# Sheet1.net
KiCad netlist of a schematic drawn in Altium Designer
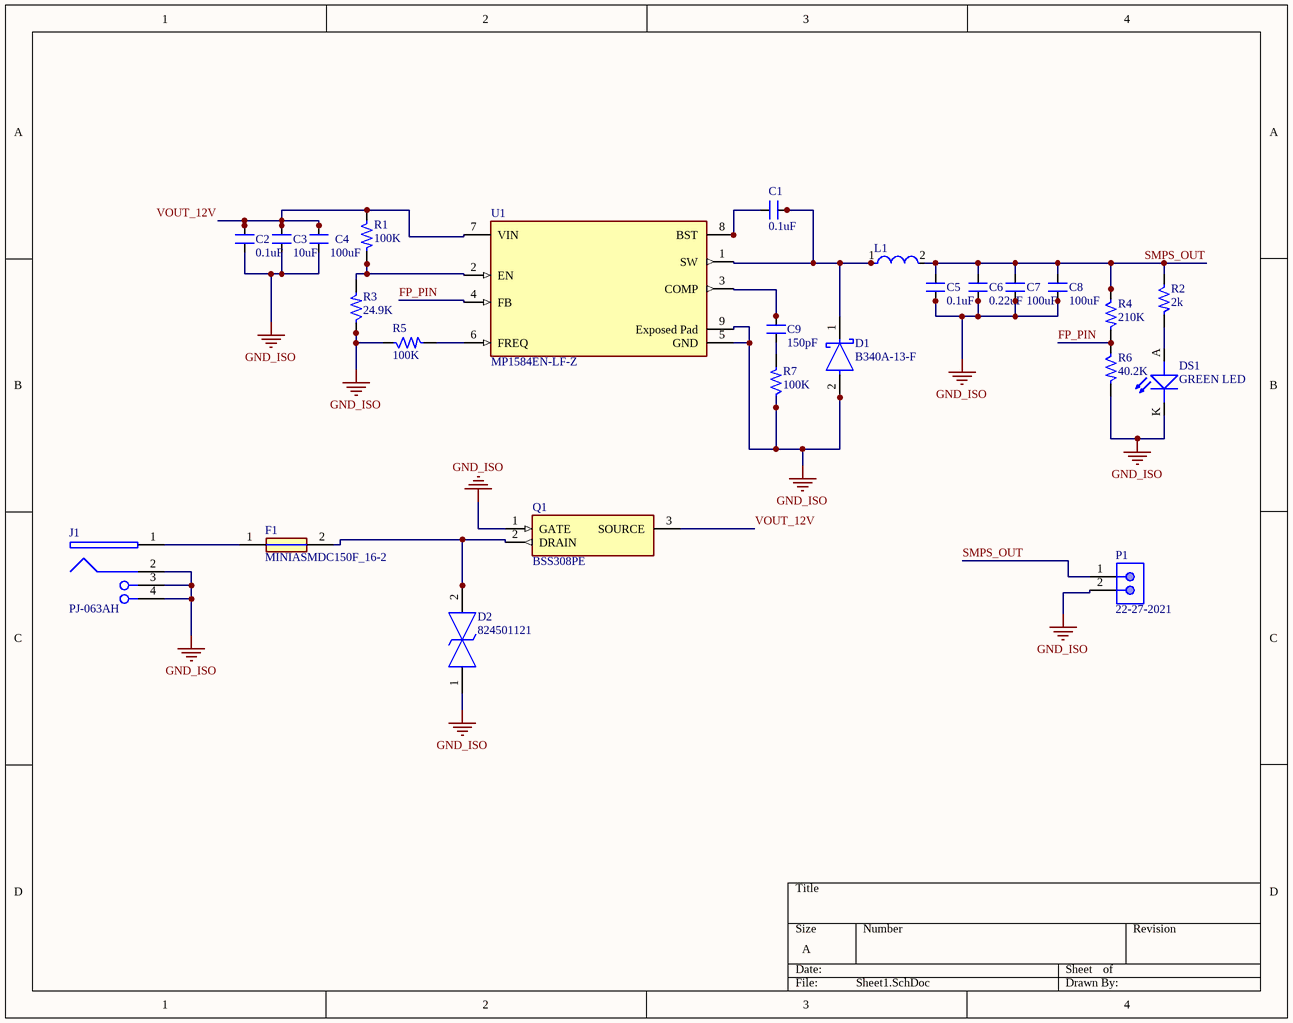
[diagram p0: Sheet1.SchDoc]

(export (version "E")
  (design (tool "Eeschema 10.0.6"))
  (components
    (comp (ref "C1")
      (value "0.1uF")
      (footprint "CAP_0805")
      (description "0.1µF ±20% 50V Ceramic Capacitor X7R 0805 (2012 Metric)")
      (fields
        (field (name "MANUFACTURER") "Samsung Electro-Mechanics")
        (field (name "MANUFACTURER PART NUMBER") "CL21B104MBCNNNC")
      )
      (libsource (lib "ESTEEMPCBLIB") (part "CAP_0.1uF-50V-20%-0805"))
    )
    (comp (ref "C2")
      (value "0.1uF")
      (footprint "CAP_0805")
      (description "0.1µF ±20% 50V Ceramic Capacitor X7R 0805 (2012 Metric)")
      (fields
        (field (name "MANUFACTURER") "Samsung Electro-Mechanics")
        (field (name "MANUFACTURER PART NUMBER") "CL21B104MBCNNNC")
      )
      (libsource (lib "ESTEEMPCBLIB") (part "CAP_0.1uF-50V-20%-0805"))
    )
    (comp (ref "C3")
      (value "10uF")
      (footprint "CAP_1206")
      (description "10µF ±10% 50V Ceramic Capacitor X7R 1206 (3216 Metric)")
      (fields
        (field (name "MANUFACTURER") "KEMET")
        (field (name "MANUFACTURER PART NUMBER") "CL31B106KBHNNNE")
      )
      (libsource (lib "ESTEEMPCBLIB") (part "CAP_10uF-50V-10%-1206"))
    )
    (comp (ref "C4")
      (value "100uF")
      (footprint "CAP_1206")
      (description "100µF ±5% 50V Ceramic Capacitor X7R 1206 (3216 Metric)")
      (fields
        (field (name "MANUFACTURER") "KEMET")
        (field (name "MANUFACTURER PART NUMBER") "C1206C104J5RACTU")
      )
      (libsource (lib "ESTEEMPCBLIB") (part "CAP_0.1uF-50V-5%-1206"))
    )
    (comp (ref "C5")
      (value "0.1uF")
      (footprint "CAP_0805")
      (description "0.1µF ±20% 50V Ceramic Capacitor X7R 0805 (2012 Metric)")
      (fields
        (field (name "MANUFACTURER") "Samsung Electro-Mechanics")
        (field (name "MANUFACTURER PART NUMBER") "CL21B104MBCNNNC")
      )
      (libsource (lib "ESTEEMPCBLIB") (part "CAP_0.1uF-50V-20%-0805"))
    )
    (comp (ref "C6")
      (value "0.22uF")
      (footprint "CAP_0805")
      (description "0.22µF ±10% 50V Ceramic Capacitor X7R 0805 (2012 Metric)")
      (fields
        (field (name "MANUFACTURER") "Murata")
        (field (name "MANUFACTURER PART NUMBER") "GRM21BR71H224KA01L")
      )
      (libsource (lib "ESTEEMPCBLIB") (part "CAP_0.22uF-50V-10%-0805"))
    )
    (comp (ref "C7")
      (value "100uF")
      (footprint "CAP_1206")
      (description "100µF ±5% 50V Ceramic Capacitor X7R 1206 (3216 Metric)")
      (fields
        (field (name "MANUFACTURER") "KEMET")
        (field (name "MANUFACTURER PART NUMBER") "C1206C104J5RACTU")
      )
      (libsource (lib "ESTEEMPCBLIB") (part "CAP_0.1uF-50V-5%-1206"))
    )
    (comp (ref "C8")
      (value "100uF")
      (footprint "CAP_1206")
      (description "100µF ±5% 50V Ceramic Capacitor X7R 1206 (3216 Metric)")
      (fields
        (field (name "MANUFACTURER") "KEMET")
        (field (name "MANUFACTURER PART NUMBER") "C1206C104J5RACTU")
      )
      (libsource (lib "ESTEEMPCBLIB") (part "CAP_0.1uF-50V-5%-1206"))
    )
    (comp (ref "C9")
      (value "150pF")
      (footprint "CAP_0805")
      (description "150pF ±10% 50V Ceramic Capacitor C0G, NP0 0805 (2012 Metric)")
      (fields
        (field (name "MANUFACTURER") "AVX Corporation")
        (field (name "MANUFACTURER PART NUMBER") "08055A151KAT2A")
      )
      (libsource (lib "ESTEEMPCBLIB") (part "CAP_150pF-50V-10%-0805"))
    )
    (comp (ref "D1")
      (value "B340A-13-F")
      (footprint "FP-SMA-MFG")
      (description "DIODE SCHOTTKY 40V 3A SMA")
      (fields (field (name "VOLTAGE") "40V"))
      (libsource (lib "Altium Content Vault") (part "1d6ec82d83fb6aee721767c19dac4b9"))
    )
    (comp (ref "D2")
      (value "824501121")
      (footprint "SamacSys:DIONM5127X250N")
      (description "TVS Diode (Bi-directional)")
      (fields (field (name "MOUSER PART NUMBER") "710-824501121"))
      (libsource (lib "*") (part "824501121"))
    )
    (comp (ref "DS1")
      (value "GREEN LED")
      (footprint "LED_0805")
      (description "Green 569nm LED Indication - Discrete 2.1V 0805 (2012 Metric)")
      (fields
        (field (name "MANUFACTURER") "Vishay Lite-On")
        (field (name "MANUFACTURER PART NUMBER") "LTST-C171GKT")
      )
      (libsource (lib "ESTEEMPCBLIB") (part "LED_GREEN-2.2-20mA-0805"))
    )
    (comp (ref "F1")
      (value "MINIASMDC150F_16-2")
      (footprint "SamacSys:FUSC4632X48N")
      (description "Fuse")
      (fields
        (field (name "MANUFACTURER_PART_NUMBER") "MINIASMDC150F/16-2")
        (field (name "MOUSER PART NUMBER") "650-MINIASMDC150F/16")
      )
      (libsource (lib "*") (part "MINIASMDC150F_16-2"))
    )
    (comp (ref "J1")
      (value "PJ-063AH")
      (footprint "CUI-PJ-063AH_V")
      (fields (field (name "MANUFACTURER") "CUIInc."))
      (libsource (lib "Altium Content Vault") (part "JACK-2CD2_A"))
    )
    (comp (ref "L1")
      (value "ETQ-P3M150KVN")
      (footprint "FP-PCC-M0630M-LP-MFG")
      (description "FIXED IND 15UH 3A 109.12 MOHM")
      (fields (field (name "MANUFACTURER") "Panasonic") (field (name "TOLERANCE") "20%"))
      (libsource (lib "Altium Content Vault") (part "725321dda6339637d4d059423bc1c3c"))
    )
    (comp (ref "P1")
      (value "22-27-2021")
      (footprint "MOLX-22-27-2021_V")
      (fields (field (name "MANUFACTURER") "Molex") (field (name "PARTNUMBER") "0022272021"))
      (libsource (lib "Altium Content Vault") (part "CN-1P-M-R2"))
    )
    (comp (ref "Q1")
      (value "BSS308PE")
      (footprint "SamacSys:SOT95P260X110-3N")
      (description "Transistor")
      (libsource (lib "*") (part "BSS308PE"))
    )
    (comp (ref "R1")
      (value "100K")
      (footprint "RES_0603")
      (description "100 kOhms ±1% 0.1W, 1/10W Chip Resistor 0603 (1608 Metric) Automotive AEC-Q200 Thick Film")
      (fields
        (field (name "MANUFACTURER") "Stackpole Electronics")
        (field (name "MANUFACTURER PART NUMBER") "RMCF0603FT100K")
      )
      (libsource (lib "ESTEEMPCBLIB") (part "RES_100K-0.1W-1%-0603"))
    )
    (comp (ref "R2")
      (value "2k")
      (footprint "RES_0603")
      (description "100 kOhms ±1% 0.1W, 1/10W Chip Resistor 0603 (1608 Metric) Automotive AEC-Q200 Thick Film")
      (fields
        (field (name "MANUFACTURER") "Stackpole Electronics")
        (field (name "MANUFACTURER PART NUMBER") "RMCF0603FT100K")
      )
      (libsource (lib "ESTEEMPCBLIB") (part "RES_100K-0.1W-1%-0603"))
    )
    (comp (ref "R3")
      (value "24.9K")
      (footprint "RES_0603")
      (description "100 kOhms ±1% 0.1W, 1/10W Chip Resistor 0603 (1608 Metric) Automotive AEC-Q200 Thick Film")
      (fields
        (field (name "MANUFACTURER") "Stackpole Electronics")
        (field (name "MANUFACTURER PART NUMBER") "RMCF0603FT100K")
      )
      (libsource (lib "ESTEEMPCBLIB") (part "RES_100K-0.1W-1%-0603"))
    )
    (comp (ref "R4")
      (value "210K")
      (footprint "RES_0603")
      (description "100 kOhms ±1% 0.1W, 1/10W Chip Resistor 0603 (1608 Metric) Automotive AEC-Q200 Thick Film")
      (fields
        (field (name "MANUFACTURER") "Stackpole Electronics")
        (field (name "MANUFACTURER PART NUMBER") "RMCF0603FT100K")
      )
      (libsource (lib "ESTEEMPCBLIB") (part "RES_100K-0.1W-1%-0603"))
    )
    (comp (ref "R5")
      (value "100K")
      (footprint "RES_0603")
      (description "100 kOhms ±1% 0.1W, 1/10W Chip Resistor 0603 (1608 Metric) Automotive AEC-Q200 Thick Film")
      (fields
        (field (name "MANUFACTURER") "Stackpole Electronics")
        (field (name "MANUFACTURER PART NUMBER") "RMCF0603FT100K")
      )
      (libsource (lib "ESTEEMPCBLIB") (part "RES_100K-0.1W-1%-0603"))
    )
    (comp (ref "R6")
      (value "40.2K")
      (footprint "RES_0603")
      (description "100 kOhms ±1% 0.1W, 1/10W Chip Resistor 0603 (1608 Metric) Automotive AEC-Q200 Thick Film")
      (fields
        (field (name "MANUFACTURER") "Stackpole Electronics")
        (field (name "MANUFACTURER PART NUMBER") "RMCF0603FT100K")
      )
      (libsource (lib "ESTEEMPCBLIB") (part "RES_100K-0.1W-1%-0603"))
    )
    (comp (ref "R7")
      (value "100K")
      (footprint "RES_0603")
      (description "100 kOhms ±1% 0.1W, 1/10W Chip Resistor 0603 (1608 Metric) Automotive AEC-Q200 Thick Film")
      (fields
        (field (name "MANUFACTURER") "Stackpole Electronics")
        (field (name "MANUFACTURER PART NUMBER") "RMCF0603FT100K")
      )
      (libsource (lib "ESTEEMPCBLIB") (part "RES_100K-0.1W-1%-0603"))
    )
    (comp (ref "U1")
      (value "MP1584EN-LF-Z")
      (footprint "FP-MP1584EN-LF-Z-MFG")
      (description "IC REG BUCK ADJ 3A")
      (fields
        (field (name "OCTOPART") "https://octopart.com/mp1584en-lf-z-monolithic+power+systems-18629680")
        (field (name "MANUFACTURER") "Monolithic Power Systems")
      )
      (libsource (lib "Altium Content Vault") (part "4a11bbc70e04dd5d8e18f8ee926335f"))
    )
  )
  (nets
    (net (code "1") (name "/FP_PIN") (class "Default")
      (node (ref "R4") (pin "2") (pinfunction "2_2") (pintype "passive"))
      (node (ref "R6") (pin "1") (pinfunction "1_1") (pintype "passive"))
      (node (ref "U1") (pin "4") (pinfunction "FB_4") (pintype "input"))
    )
    (net (code "2") (name "/SMPS_OUT") (class "Default")
      (node (ref "C5") (pin "2") (pinfunction "2_2") (pintype "passive"))
      (node (ref "C6") (pin "2") (pinfunction "2_2") (pintype "passive"))
      (node (ref "C7") (pin "2") (pinfunction "2_2") (pintype "passive"))
      (node (ref "C8") (pin "2") (pinfunction "2_2") (pintype "passive"))
      (node (ref "L1") (pin "2") (pinfunction "2_2") (pintype "passive"))
      (node (ref "P1") (pin "1") (pinfunction "1_1") (pintype "passive"))
      (node (ref "R2") (pin "1") (pinfunction "1_1") (pintype "passive"))
      (node (ref "R4") (pin "1") (pinfunction "1_1") (pintype "passive"))
    )
    (net (code "3") (name "/VOUT_12V") (class "Default")
      (node (ref "C2") (pin "2") (pinfunction "2_2") (pintype "passive"))
      (node (ref "C3") (pin "2") (pinfunction "2_2") (pintype "passive"))
      (node (ref "C4") (pin "2") (pinfunction "2_2") (pintype "passive"))
      (node (ref "Q1") (pin "3") (pinfunction "SOURCE_3") (pintype "passive"))
      (node (ref "R1") (pin "1") (pinfunction "1_1") (pintype "passive"))
      (node (ref "U1") (pin "7") (pinfunction "VIN_7") (pintype "power_in"))
    )
    (net (code "4") (name "GND_ISO") (class "Default")
      (node (ref "C2") (pin "1") (pinfunction "1_1") (pintype "passive"))
      (node (ref "C3") (pin "1") (pinfunction "1_1") (pintype "passive"))
      (node (ref "C4") (pin "1") (pinfunction "1_1") (pintype "passive"))
      (node (ref "C5") (pin "1") (pinfunction "1_1") (pintype "passive"))
      (node (ref "C6") (pin "1") (pinfunction "1_1") (pintype "passive"))
      (node (ref "C7") (pin "1") (pinfunction "1_1") (pintype "passive"))
      (node (ref "C8") (pin "1") (pinfunction "1_1") (pintype "passive"))
      (node (ref "D1") (pin "2") (pinfunction "A_2") (pintype "passive"))
      (node (ref "D2") (pin "1") (pinfunction "1_1") (pintype "passive"))
      (node (ref "DS1") (pin "K") (pinfunction "CATHODE_K") (pintype "passive"))
      (node (ref "J1") (pin "2") (pinfunction "2_2") (pintype "passive"))
      (node (ref "J1") (pin "3") (pinfunction "SHLD_3") (pintype "passive"))
      (node (ref "J1") (pin "4") (pinfunction "SHLD_4") (pintype "passive"))
      (node (ref "P1") (pin "2") (pinfunction "2_2") (pintype "passive"))
      (node (ref "Q1") (pin "1") (pinfunction "GATE_1") (pintype "input"))
      (node (ref "R3") (pin "1") (pinfunction "1_1") (pintype "passive"))
      (node (ref "R5") (pin "1") (pinfunction "1_1") (pintype "passive"))
      (node (ref "R6") (pin "2") (pinfunction "2_2") (pintype "passive"))
      (node (ref "R7") (pin "1") (pinfunction "1_1") (pintype "passive"))
      (node (ref "U1") (pin "5") (pinfunction "GND_5") (pintype "power_in"))
      (node (ref "U1") (pin "9") (pinfunction "Exposed_Pad_9") (pintype "power_in"))
    )
    (net (code "5") (name "Net-(C9-Pad1)") (class "Default")
      (node (ref "C9") (pin "1") (pinfunction "1_1") (pintype "passive"))
      (node (ref "R7") (pin "2") (pinfunction "2_2") (pintype "passive"))
    )
    (net (code "6") (name "Net-(D1-C)") (class "Default")
      (node (ref "C1") (pin "1") (pinfunction "1_1") (pintype "passive"))
      (node (ref "D1") (pin "1") (pinfunction "C_1") (pintype "passive"))
      (node (ref "L1") (pin "1") (pinfunction "1_1") (pintype "passive"))
      (node (ref "U1") (pin "1") (pinfunction "SW_1") (pintype "output"))
    )
    (net (code "7") (name "Net-(DS1-ANODE)") (class "Default")
      (node (ref "DS1") (pin "A") (pinfunction "ANODE_A") (pintype "passive"))
      (node (ref "R2") (pin "2") (pinfunction "2_2") (pintype "passive"))
    )
    (net (code "8") (name "Net-(F1-Pad1)") (class "Default")
      (node (ref "F1") (pin "1") (pinfunction "1_1") (pintype "passive"))
      (node (ref "J1") (pin "1") (pinfunction "1_1") (pintype "passive"))
    )
    (net (code "9") (name "Net-(Q1-DRAIN)") (class "Default")
      (node (ref "D2") (pin "2") (pinfunction "2_2") (pintype "passive"))
      (node (ref "F1") (pin "2") (pinfunction "2_2") (pintype "passive"))
      (node (ref "Q1") (pin "2") (pinfunction "DRAIN_2") (pintype "output"))
    )
    (net (code "10") (name "Net-(U1-BST)") (class "Default")
      (node (ref "C1") (pin "2") (pinfunction "2_2") (pintype "passive"))
      (node (ref "U1") (pin "8") (pinfunction "BST_8") (pintype "power_in"))
    )
    (net (code "11") (name "Net-(U1-COMP)") (class "Default")
      (node (ref "C9") (pin "2") (pinfunction "2_2") (pintype "passive"))
      (node (ref "U1") (pin "3") (pinfunction "COMP_3") (pintype "output"))
    )
    (net (code "12") (name "Net-(U1-EN)") (class "Default")
      (node (ref "R1") (pin "2") (pinfunction "2_2") (pintype "passive"))
      (node (ref "R3") (pin "2") (pinfunction "2_2") (pintype "passive"))
      (node (ref "U1") (pin "2") (pinfunction "EN_2") (pintype "input"))
    )
    (net (code "13") (name "Net-(U1-FREQ)") (class "Default")
      (node (ref "R5") (pin "2") (pinfunction "2_2") (pintype "passive"))
      (node (ref "U1") (pin "6") (pinfunction "FREQ_6") (pintype "input"))
    )
  )
)
